# wifiboard-v2.net
KiCad netlist of a schematic drawn in EAGLE
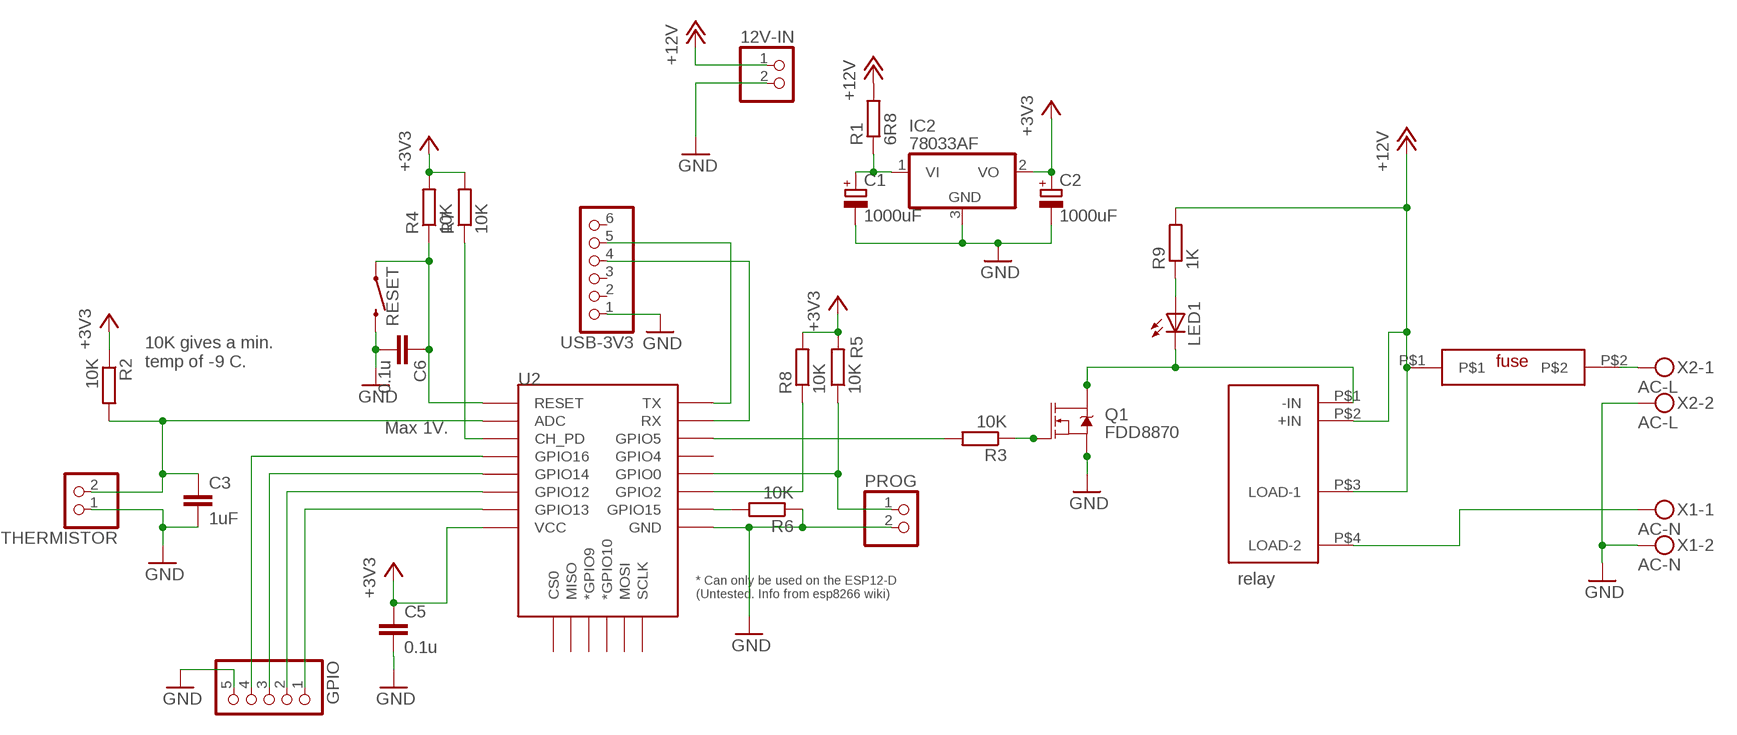
[diagram p0: schematic, sheet 1]

(export (version "E")
  (design (tool "Eeschema 10.0.6"))
  (components
    (comp (ref "12V-IN")
      (value "PINHD-1X2")
      (footprint "eagle-import:1X02")
      (libsource (lib "eagle-import") (part "PINHD-1X2"))
    )
    (comp (ref "C1")
      (value "1000uF")
      (footprint "eagle-import:B45181B")
      (libsource (lib "eagle-import") (part "CPOL-EUB45181B"))
    )
    (comp (ref "C2")
      (value "1000uF")
      (footprint "eagle-import:B45181B")
      (libsource (lib "eagle-import") (part "CPOL-EUB45181B"))
    )
    (comp (ref "C3")
      (value "1uF")
      (footprint "eagle-import:C0805")
      (libsource (lib "eagle-import") (part "C-EUC0805"))
    )
    (comp (ref "C5")
      (value "0.1u")
      (footprint "eagle-import:C0805")
      (libsource (lib "eagle-import") (part "C-EUC0805"))
    )
    (comp (ref "C6")
      (value "0.1u")
      (footprint "eagle-import:C0805")
      (libsource (lib "eagle-import") (part "C-EUC0805"))
    )
    (comp (ref "FUSE")
      (value "FUSE")
      (footprint "eagle-import:FUSE")
      (libsource (lib "eagle-import") (part "FUSE"))
    )
    (comp (ref "GPIO")
      (value "PINHD-1X5")
      (footprint "eagle-import:1X05")
      (libsource (lib "eagle-import") (part "PINHD-1X5"))
    )
    (comp (ref "IC2")
      (value "78033AF")
      (footprint "eagle-import:TO252")
      (libsource (lib "eagle-import") (part "78DT05"))
    )
    (comp (ref "LED1")
      (value "LED3MM")
      (footprint "eagle-import:LED3MM")
      (libsource (lib "eagle-import") (part "LED3MM"))
    )
    (comp (ref "PROG")
      (value "PINHD-1X2")
      (footprint "eagle-import:1X02")
      (libsource (lib "eagle-import") (part "PINHD-1X2"))
    )
    (comp (ref "Q1")
      (value "FDD8870")
      (footprint "eagle-import:DPAK")
      (libsource (lib "eagle-import") (part "MOSFET-NCH-FDD8780"))
    )
    (comp (ref "R1")
      (value "6R8")
      (footprint "eagle-import:0207_10")
      (libsource (lib "eagle-import") (part "R-EU_0207/10"))
    )
    (comp (ref "R2")
      (value "10K")
      (footprint "eagle-import:M0805")
      (libsource (lib "eagle-import") (part "R-EU_M0805"))
    )
    (comp (ref "R3")
      (value "10K")
      (footprint "eagle-import:M0805")
      (libsource (lib "eagle-import") (part "R-EU_M0805"))
    )
    (comp (ref "R4")
      (value "10K")
      (footprint "eagle-import:R0805")
      (libsource (lib "eagle-import") (part "R-EU_R0805"))
    )
    (comp (ref "R5")
      (value "10K")
      (footprint "eagle-import:R0805")
      (libsource (lib "eagle-import") (part "R-EU_R0805"))
    )
    (comp (ref "R6")
      (value "10K")
      (footprint "eagle-import:R0805")
      (libsource (lib "eagle-import") (part "R-EU_R0805"))
    )
    (comp (ref "R7")
      (value "10K")
      (footprint "eagle-import:R0805")
      (libsource (lib "eagle-import") (part "R-EU_R0805"))
    )
    (comp (ref "R8")
      (value "10K")
      (footprint "eagle-import:R0805")
      (libsource (lib "eagle-import") (part "R-EU_R0805"))
    )
    (comp (ref "R9")
      (value "1K")
      (footprint "eagle-import:R0805")
      (libsource (lib "eagle-import") (part "R-EU_R0805"))
    )
    (comp (ref "RELAY")
      (value "OMRON-G6DS")
      (footprint "eagle-import:OMRON-G6DS-1A-H")
      (libsource (lib "eagle-import") (part "OMRON-G6DS"))
    )
    (comp (ref "RESET")
      (value "MOMENTARY-SWITCH-SPST-SMD-4.6X2.8MM")
      (footprint "eagle-import:TACTILE_SWITCH_SMD_4.6X2.8MM")
      (libsource (lib "eagle-import") (part "MOMENTARY-SWITCH-SPST-SMD-4.6X2.8MM"))
    )
    (comp (ref "THERMISTOR")
      (value "PINHD-1X2")
      (footprint "eagle-import:1X02")
      (libsource (lib "eagle-import") (part "PINHD-1X2"))
    )
    (comp (ref "U2")
      (value "ESP12ESMD")
      (footprint "eagle-import:ESP12E-SMD")
      (libsource (lib "eagle-import") (part "ESP12ESMD"))
    )
    (comp (ref "USB-3V3")
      (value "PINHD-1X6")
      (footprint "eagle-import:1X06")
      (libsource (lib "eagle-import") (part "PINHD-1X6"))
    )
    (comp (ref "X1")
      (value "AC-N")
      (footprint "eagle-import:MKDSN1,5_2-5,08")
      (libsource (lib "eagle-import") (part "MKDSN1,5/2-5,08"))
    )
    (comp (ref "X2")
      (value "AC-L")
      (footprint "eagle-import:MKDSN1,5_2-5,08")
      (libsource (lib "eagle-import") (part "MKDSN1,5/2-5,08"))
    )
  )
  (nets
    (net (code "1") (name "+3V3") (class "Default")
      (node (ref "C2") (pin "+") (pinfunction "+_+") (pintype "passive"))
      (node (ref "C5") (pin "1") (pinfunction "1_1") (pintype "passive"))
      (node (ref "IC2") (pin "2") (pinfunction "VO_2") (pintype "passive"))
      (node (ref "R2") (pin "1") (pinfunction "1_1") (pintype "passive"))
      (node (ref "R4") (pin "2") (pinfunction "2_2") (pintype "passive"))
      (node (ref "R5") (pin "2") (pinfunction "2_2") (pintype "passive"))
      (node (ref "R7") (pin "2") (pinfunction "2_2") (pintype "passive"))
      (node (ref "R8") (pin "2") (pinfunction "2_2") (pintype "passive"))
      (node (ref "U2") (pin "VCC") (pinfunction "VCC_VCC") (pintype "bidirectional"))
    )
    (net (code "2") (name "+12V") (class "Default")
      (node (ref "12V-IN") (pin "1") (pinfunction "1_1") (pintype "passive"))
      (node (ref "FUSE") (pin "P$1") (pinfunction "P$1_P$1") (pintype "bidirectional"))
      (node (ref "R1") (pin "2") (pinfunction "2_2") (pintype "passive"))
      (node (ref "R9") (pin "2") (pinfunction "2_2") (pintype "passive"))
      (node (ref "RELAY") (pin "P$2") (pinfunction "+IN_P$2") (pintype "input"))
      (node (ref "RELAY") (pin "P$3") (pinfunction "LOAD-1_P$3") (pintype "bidirectional"))
    )
    (net (code "3") (name "GND") (class "Default")
      (node (ref "12V-IN") (pin "2") (pinfunction "2_2") (pintype "passive"))
      (node (ref "C1") (pin "-") (pinfunction "-_-") (pintype "passive"))
      (node (ref "C2") (pin "-") (pinfunction "-_-") (pintype "passive"))
      (node (ref "C3") (pin "2") (pinfunction "2_2") (pintype "passive"))
      (node (ref "C5") (pin "2") (pinfunction "2_2") (pintype "passive"))
      (node (ref "C6") (pin "2") (pinfunction "2_2") (pintype "passive"))
      (node (ref "GPIO") (pin "5") (pinfunction "5_5") (pintype "passive"))
      (node (ref "IC2") (pin "3") (pinfunction "GND_3") (pintype "passive"))
      (node (ref "PROG") (pin "2") (pinfunction "2_2") (pintype "passive"))
      (node (ref "Q1") (pin "3") (pinfunction "S_3") (pintype "bidirectional"))
      (node (ref "R6") (pin "1") (pinfunction "1_1") (pintype "passive"))
      (node (ref "RESET") (pin "3") (pinfunction "2_3") (pintype "passive"))
      (node (ref "RESET") (pin "4") (pinfunction "2_4") (pintype "passive"))
      (node (ref "THERMISTOR") (pin "1") (pinfunction "1_1") (pintype "passive"))
      (node (ref "U2") (pin "GND") (pinfunction "GND_GND") (pintype "bidirectional"))
      (node (ref "USB-3V3") (pin "1") (pinfunction "1_1") (pintype "passive"))
      (node (ref "X1") (pin "2") (pinfunction "KL_2") (pintype "passive"))
      (node (ref "X2") (pin "2") (pinfunction "KL_2") (pintype "passive"))
    )
    (net (code "4") (name "Net-(C3-Pad1)") (class "Default")
      (node (ref "C3") (pin "1") (pinfunction "1_1") (pintype "passive"))
      (node (ref "R2") (pin "2") (pinfunction "2_2") (pintype "passive"))
      (node (ref "THERMISTOR") (pin "2") (pinfunction "2_2") (pintype "passive"))
      (node (ref "U2") (pin "ADC") (pinfunction "ADC_ADC") (pintype "bidirectional"))
    )
    (net (code "5") (name "Net-(C6-Pad1)") (class "Default")
      (node (ref "C6") (pin "1") (pinfunction "1_1") (pintype "passive"))
      (node (ref "R4") (pin "1") (pinfunction "1_1") (pintype "passive"))
      (node (ref "RESET") (pin "1") (pinfunction "1_1") (pintype "passive"))
      (node (ref "RESET") (pin "2") (pinfunction "1_2") (pintype "passive"))
      (node (ref "U2") (pin "RESET") (pinfunction "RESET_RESET") (pintype "bidirectional"))
    )
    (net (code "6") (name "Net-(GPIO-Pad1)") (class "Default")
      (node (ref "GPIO") (pin "1") (pinfunction "1_1") (pintype "passive"))
      (node (ref "U2") (pin "GPIO13") (pinfunction "GPIO13_GPIO13") (pintype "bidirectional"))
    )
    (net (code "7") (name "Net-(GPIO-Pad2)") (class "Default")
      (node (ref "GPIO") (pin "2") (pinfunction "2_2") (pintype "passive"))
      (node (ref "U2") (pin "GPIO12") (pinfunction "GPIO12_GPIO12") (pintype "bidirectional"))
    )
    (net (code "8") (name "Net-(GPIO-Pad3)") (class "Default")
      (node (ref "GPIO") (pin "3") (pinfunction "3_3") (pintype "passive"))
      (node (ref "U2") (pin "GPIO14") (pinfunction "GPIO14_GPIO14") (pintype "bidirectional"))
    )
    (net (code "9") (name "Net-(GPIO-Pad4)") (class "Default")
      (node (ref "GPIO") (pin "4") (pinfunction "4_4") (pintype "passive"))
      (node (ref "U2") (pin "GPIO16") (pinfunction "GPIO16_GPIO16") (pintype "bidirectional"))
    )
    (net (code "10") (name "Net-(IC2-VI)") (class "Default")
      (node (ref "C1") (pin "+") (pinfunction "+_+") (pintype "passive"))
      (node (ref "IC2") (pin "1") (pinfunction "VI_1") (pintype "input"))
      (node (ref "R1") (pin "1") (pinfunction "1_1") (pintype "passive"))
    )
    (net (code "11") (name "Net-(LED1-C)") (class "Default")
      (node (ref "LED1") (pin "K") (pinfunction "C_K") (pintype "passive"))
      (node (ref "Q1") (pin "4") (pinfunction "D_4") (pintype "bidirectional"))
      (node (ref "RELAY") (pin "P$1") (pinfunction "-IN_P$1") (pintype "input"))
    )
    (net (code "12") (name "Net-(LED1-PadA)") (class "Default")
      (node (ref "LED1") (pin "A") (pinfunction "A_A") (pintype "passive"))
      (node (ref "R9") (pin "1") (pinfunction "1_1") (pintype "passive"))
    )
    (net (code "13") (name "Net-(PROG-Pad1)") (class "Default")
      (node (ref "PROG") (pin "1") (pinfunction "1_1") (pintype "passive"))
      (node (ref "R5") (pin "1") (pinfunction "1_1") (pintype "passive"))
      (node (ref "U2") (pin "GPIO0") (pinfunction "GPIO0_GPIO0") (pintype "bidirectional"))
    )
    (net (code "14") (name "Net-(Q1-G)") (class "Default")
      (node (ref "Q1") (pin "1") (pinfunction "G_1") (pintype "bidirectional"))
      (node (ref "R3") (pin "1") (pinfunction "1_1") (pintype "passive"))
    )
    (net (code "15") (name "Net-(R3-Pad2)") (class "Default")
      (node (ref "R3") (pin "2") (pinfunction "2_2") (pintype "passive"))
      (node (ref "U2") (pin "GPIO5") (pinfunction "GPIO5_GPIO5") (pintype "bidirectional"))
    )
    (net (code "16") (name "Net-(R6-Pad2)") (class "Default")
      (node (ref "R6") (pin "2") (pinfunction "2_2") (pintype "passive"))
      (node (ref "U2") (pin "GPIO15") (pinfunction "GPIO15_GPIO15") (pintype "bidirectional"))
    )
    (net (code "17") (name "Net-(R7-Pad1)") (class "Default")
      (node (ref "R7") (pin "1") (pinfunction "1_1") (pintype "passive"))
      (node (ref "U2") (pin "CH_PD") (pinfunction "CH_PD_CH_PD") (pintype "bidirectional"))
    )
    (net (code "18") (name "Net-(R8-Pad1)") (class "Default")
      (node (ref "R8") (pin "1") (pinfunction "1_1") (pintype "passive"))
      (node (ref "U2") (pin "GPIO2") (pinfunction "GPIO2_GPIO2") (pintype "bidirectional"))
    )
    (net (code "19") (name "Net-(RELAY-LOAD-2)") (class "Default")
      (node (ref "RELAY") (pin "P$4") (pinfunction "LOAD-2_P$4") (pintype "bidirectional"))
      (node (ref "X1") (pin "1") (pinfunction "KL_1") (pintype "passive"))
    )
    (net (code "20") (name "Net-(U2-RX)") (class "Default")
      (node (ref "U2") (pin "RXD0") (pinfunction "RX_RXD0") (pintype "bidirectional"))
      (node (ref "USB-3V3") (pin "4") (pinfunction "4_4") (pintype "passive"))
    )
    (net (code "21") (name "Net-(U2-TX)") (class "Default")
      (node (ref "U2") (pin "TXD0") (pinfunction "TX_TXD0") (pintype "bidirectional"))
      (node (ref "USB-3V3") (pin "5") (pinfunction "5_5") (pintype "passive"))
    )
    (net (code "22") (name "Net-(X2A-KL)") (class "Default")
      (node (ref "FUSE") (pin "P$2") (pinfunction "P$2_P$2") (pintype "bidirectional"))
      (node (ref "X2") (pin "1") (pinfunction "KL_1") (pintype "passive"))
    )
    (net (code "23") (name "unconnected-(U2-*GPIO9-PadGPIO9)") (class "Default")
      (node (ref "U2") (pin "GPIO9") (pinfunction "*GPIO9_GPIO9") (pintype "bidirectional"))
    )
    (net (code "24") (name "unconnected-(U2-*GPIO10-PadGPIO10)") (class "Default")
      (node (ref "U2") (pin "GPIO10") (pinfunction "*GPIO10_GPIO10") (pintype "bidirectional"))
    )
    (net (code "25") (name "unconnected-(U2-PadCS0)") (class "Default")
      (node (ref "U2") (pin "CS0") (pinfunction "CS0_CS0") (pintype "bidirectional"))
    )
    (net (code "26") (name "unconnected-(U2-PadGPIO4)") (class "Default")
      (node (ref "U2") (pin "GPIO4") (pinfunction "GPIO4_GPIO4") (pintype "bidirectional"))
    )
    (net (code "27") (name "unconnected-(U2-PadMISO)") (class "Default")
      (node (ref "U2") (pin "MISO") (pinfunction "MISO_MISO") (pintype "bidirectional"))
    )
    (net (code "28") (name "unconnected-(U2-PadMOSI)") (class "Default")
      (node (ref "U2") (pin "MOSI") (pinfunction "MOSI_MOSI") (pintype "bidirectional"))
    )
    (net (code "29") (name "unconnected-(U2-PadSCLK)") (class "Default")
      (node (ref "U2") (pin "SCLK") (pinfunction "SCLK_SCLK") (pintype "bidirectional"))
    )
    (net (code "30") (name "unconnected-(USB-3V3-Pad2)") (class "Default")
      (node (ref "USB-3V3") (pin "2") (pinfunction "2_2") (pintype "passive"))
    )
    (net (code "31") (name "unconnected-(USB-3V3-Pad3)") (class "Default")
      (node (ref "USB-3V3") (pin "3") (pinfunction "3_3") (pintype "passive"))
    )
    (net (code "32") (name "unconnected-(USB-3V3-Pad6)") (class "Default")
      (node (ref "USB-3V3") (pin "6") (pinfunction "6_6") (pintype "passive"))
    )
  )
)
